# Anode.net
KiCad netlist of a schematic drawn in Altium Designer
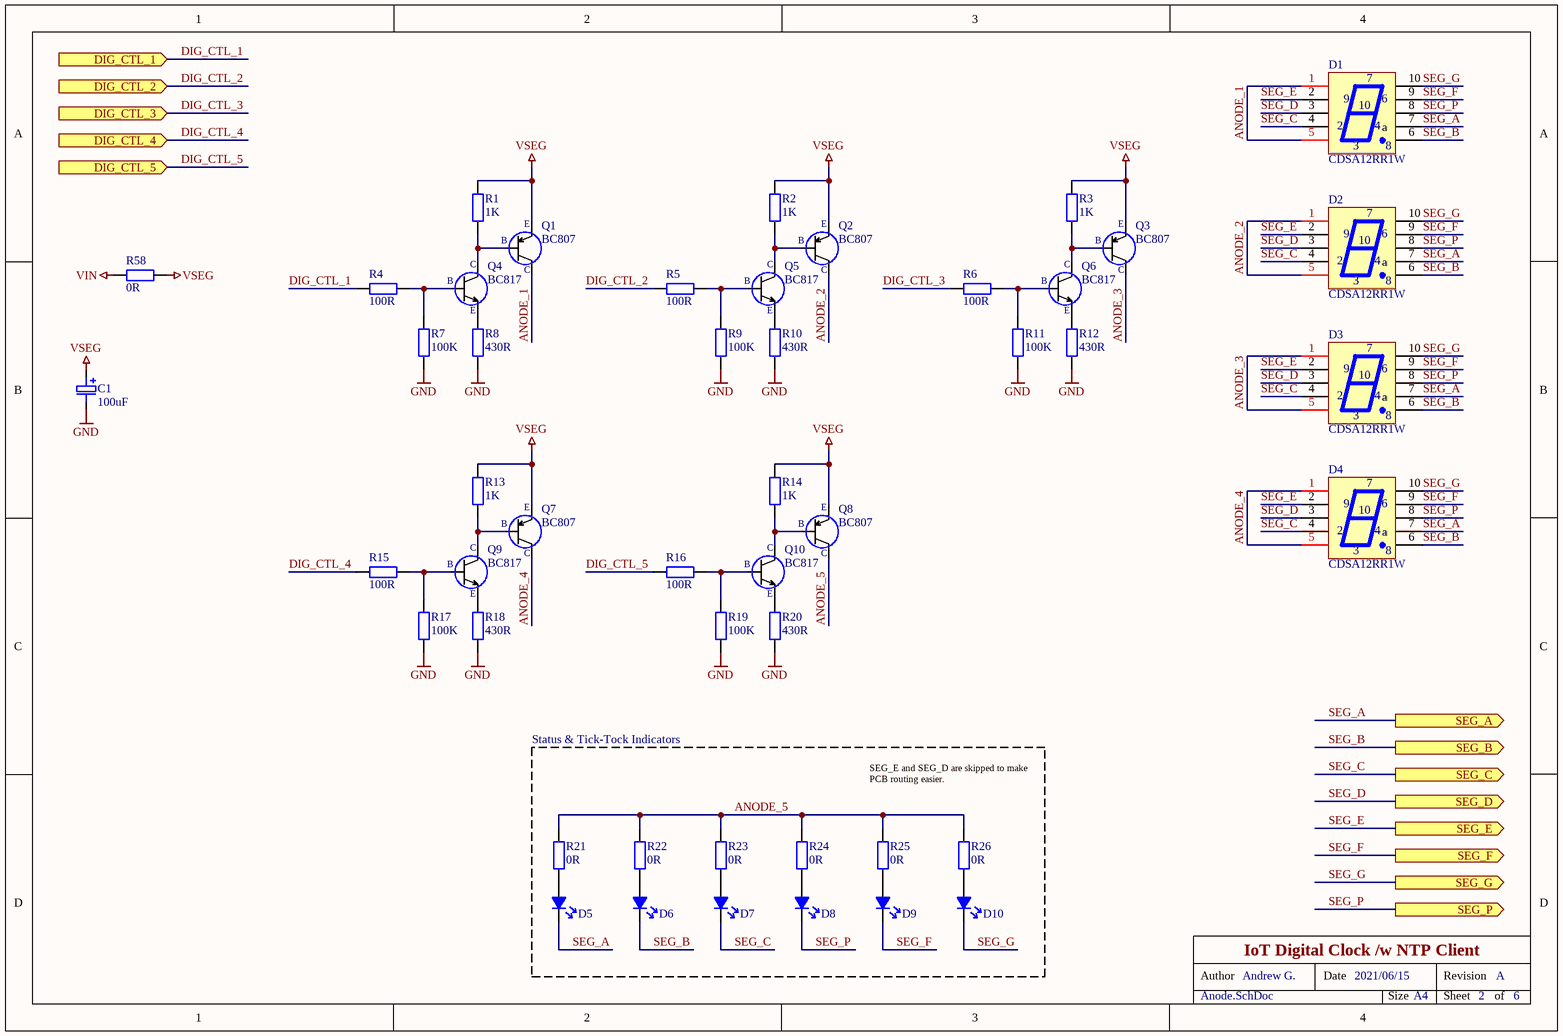
[diagram p0: Anode.SchDoc]

(export (version "E")
  (design (tool "Eeschema 10.0.6"))
  (components
    (comp (ref "C1")
      (value "100uF")
      (footprint "C_EL_B_4MM_RF_M")
      (description "Polarized Capacitor")
      (fields (field (name "TOLERANCE") "?") (field (name "MANUFACTURER") "Generic Brand"))
      (libsource (lib "AG.Generic") (part "C-P"))
    )
    (comp (ref "D1")
      (value "CDSA12RR1W")
      (footprint "CDSX12")
      (description "DISPLAY 7SEG 1.20\" SGL RED 10DIP")
      (libsource (lib "AG.Passive") (part "CDSA12RR1W"))
    )
    (comp (ref "D2")
      (value "CDSA12RR1W")
      (footprint "CDSX12")
      (description "DISPLAY 7SEG 1.20\" SGL RED 10DIP")
      (libsource (lib "AG.Passive") (part "CDSA12RR1W"))
    )
    (comp (ref "D3")
      (value "CDSA12RR1W")
      (footprint "CDSX12")
      (description "DISPLAY 7SEG 1.20\" SGL RED 10DIP")
      (libsource (lib "AG.Passive") (part "CDSA12RR1W"))
    )
    (comp (ref "D4")
      (value "CDSA12RR1W")
      (footprint "CDSX12")
      (description "DISPLAY 7SEG 1.20\" SGL RED 10DIP")
      (libsource (lib "AG.Passive") (part "CDSA12RR1W"))
    )
    (comp (ref "D5")
      (value "Unspecified")
      (footprint "1206LED_RF_M")
      (description "LED")
      (fields (field (name "MANUFACTURER") "Generic Brand"))
      (libsource (lib "AG.Generic") (part "LED"))
    )
    (comp (ref "D6")
      (value "Unspecified")
      (footprint "1206LED_RF_M")
      (description "LED")
      (fields (field (name "MANUFACTURER") "Generic Brand"))
      (libsource (lib "AG.Generic") (part "LED"))
    )
    (comp (ref "D7")
      (value "Unspecified")
      (footprint "1206LED_RF_M")
      (description "LED")
      (fields (field (name "MANUFACTURER") "Generic Brand"))
      (libsource (lib "AG.Generic") (part "LED"))
    )
    (comp (ref "D8")
      (value "Unspecified")
      (footprint "1206LED_RF_M")
      (description "LED")
      (fields (field (name "MANUFACTURER") "Generic Brand"))
      (libsource (lib "AG.Generic") (part "LED"))
    )
    (comp (ref "D9")
      (value "Unspecified")
      (footprint "1206LED_RF_M")
      (description "LED")
      (fields (field (name "MANUFACTURER") "Generic Brand"))
      (libsource (lib "AG.Generic") (part "LED"))
    )
    (comp (ref "D10")
      (value "Unspecified")
      (footprint "1206LED_RF_M")
      (description "LED")
      (fields (field (name "MANUFACTURER") "Generic Brand"))
      (libsource (lib "AG.Generic") (part "LED"))
    )
    (comp (ref "Q1")
      (value "BC807")
      (footprint "IRLML_SOT-23")
      (description "TRANS PNP 45V 500MA TO236AB")
      (fields (field (name "ALTERNATIVE SUPPLIER PART NO") "9000113306"))
      (libsource (lib "AG.Discrete") (part "BC807-215"))
    )
    (comp (ref "Q2")
      (value "BC807")
      (footprint "IRLML_SOT-23")
      (description "TRANS PNP 45V 500MA TO236AB")
      (fields (field (name "ALTERNATIVE SUPPLIER PART NO") "9000113306"))
      (libsource (lib "AG.Discrete") (part "BC807-215"))
    )
    (comp (ref "Q3")
      (value "BC807")
      (footprint "IRLML_SOT-23")
      (description "TRANS PNP 45V 500MA TO236AB")
      (fields (field (name "ALTERNATIVE SUPPLIER PART NO") "9000113306"))
      (libsource (lib "AG.Discrete") (part "BC807-215"))
    )
    (comp (ref "Q4")
      (value "BC817")
      (footprint "IRLML_SOT-23")
      (description "TRANS NPN 45V 0.5A SOT23")
      (fields
        (field (name "MANUFACTURER") "Nexperia USA Inc.")
        (field (name "MANUFACTURER PART NO") "BC817-40,215")
      )
      (libsource (lib "AG.Discrete") (part "BC817-40-215"))
    )
    (comp (ref "Q5")
      (value "BC817")
      (footprint "IRLML_SOT-23")
      (description "TRANS NPN 45V 0.5A SOT23")
      (fields
        (field (name "MANUFACTURER") "Nexperia USA Inc.")
        (field (name "MANUFACTURER PART NO") "BC817-40,215")
      )
      (libsource (lib "AG.Discrete") (part "BC817-40-215"))
    )
    (comp (ref "Q6")
      (value "BC817")
      (footprint "IRLML_SOT-23")
      (description "TRANS NPN 45V 0.5A SOT23")
      (fields
        (field (name "MANUFACTURER") "Nexperia USA Inc.")
        (field (name "MANUFACTURER PART NO") "BC817-40,215")
      )
      (libsource (lib "AG.Discrete") (part "BC817-40-215"))
    )
    (comp (ref "Q7")
      (value "BC807")
      (footprint "IRLML_SOT-23")
      (description "TRANS PNP 45V 500MA TO236AB")
      (fields (field (name "ALTERNATIVE SUPPLIER PART NO") "9000113306"))
      (libsource (lib "AG.Discrete") (part "BC807-215"))
    )
    (comp (ref "Q8")
      (value "BC807")
      (footprint "IRLML_SOT-23")
      (description "TRANS PNP 45V 500MA TO236AB")
      (fields (field (name "ALTERNATIVE SUPPLIER PART NO") "9000113306"))
      (libsource (lib "AG.Discrete") (part "BC807-215"))
    )
    (comp (ref "Q9")
      (value "BC817")
      (footprint "IRLML_SOT-23")
      (description "TRANS NPN 45V 0.5A SOT23")
      (fields
        (field (name "MANUFACTURER") "Nexperia USA Inc.")
        (field (name "MANUFACTURER PART NO") "BC817-40,215")
      )
      (libsource (lib "AG.Discrete") (part "BC817-40-215"))
    )
    (comp (ref "Q10")
      (value "BC817")
      (footprint "IRLML_SOT-23")
      (description "TRANS NPN 45V 0.5A SOT23")
      (fields
        (field (name "MANUFACTURER") "Nexperia USA Inc.")
        (field (name "MANUFACTURER PART NO") "BC817-40,215")
      )
      (libsource (lib "AG.Discrete") (part "BC817-40-215"))
    )
    (comp (ref "R1")
      (value "1K")
      (footprint "0805R_RF_M")
      (description "Resistor")
      (fields (field (name "TOLERANCE") "?") (field (name "MANUFACTURER") "Generic Brand"))
      (libsource (lib "AG.Generic") (part "R"))
    )
    (comp (ref "R2")
      (value "1K")
      (footprint "0805R_RF_M")
      (description "Resistor")
      (fields (field (name "TOLERANCE") "?") (field (name "MANUFACTURER") "Generic Brand"))
      (libsource (lib "AG.Generic") (part "R"))
    )
    (comp (ref "R3")
      (value "1K")
      (footprint "0805R_RF_M")
      (description "Resistor")
      (fields (field (name "TOLERANCE") "?") (field (name "MANUFACTURER") "Generic Brand"))
      (libsource (lib "AG.Generic") (part "R"))
    )
    (comp (ref "R4")
      (value "100R")
      (footprint "0805R_RF_M")
      (description "Resistor")
      (fields (field (name "TOLERANCE") "?") (field (name "MANUFACTURER") "Generic Brand"))
      (libsource (lib "AG.Generic") (part "R"))
    )
    (comp (ref "R5")
      (value "100R")
      (footprint "0805R_RF_M")
      (description "Resistor")
      (fields (field (name "TOLERANCE") "?") (field (name "MANUFACTURER") "Generic Brand"))
      (libsource (lib "AG.Generic") (part "R"))
    )
    (comp (ref "R6")
      (value "100R")
      (footprint "0805R_RF_M")
      (description "Resistor")
      (fields (field (name "TOLERANCE") "?") (field (name "MANUFACTURER") "Generic Brand"))
      (libsource (lib "AG.Generic") (part "R"))
    )
    (comp (ref "R7")
      (value "100K")
      (footprint "0805R_RF_M")
      (description "Resistor")
      (fields (field (name "TOLERANCE") "?") (field (name "MANUFACTURER") "Generic Brand"))
      (libsource (lib "AG.Generic") (part "R"))
    )
    (comp (ref "R8")
      (value "430R")
      (footprint "0805R_RF_M")
      (description "Resistor")
      (fields (field (name "TOLERANCE") "?") (field (name "MANUFACTURER") "Generic Brand"))
      (libsource (lib "AG.Generic") (part "R"))
    )
    (comp (ref "R9")
      (value "100K")
      (footprint "0805R_RF_M")
      (description "Resistor")
      (fields (field (name "TOLERANCE") "?") (field (name "MANUFACTURER") "Generic Brand"))
      (libsource (lib "AG.Generic") (part "R"))
    )
    (comp (ref "R10")
      (value "430R")
      (footprint "0805R_RF_M")
      (description "Resistor")
      (fields (field (name "TOLERANCE") "?") (field (name "MANUFACTURER") "Generic Brand"))
      (libsource (lib "AG.Generic") (part "R"))
    )
    (comp (ref "R11")
      (value "100K")
      (footprint "0805R_RF_M")
      (description "Resistor")
      (fields (field (name "TOLERANCE") "?") (field (name "MANUFACTURER") "Generic Brand"))
      (libsource (lib "AG.Generic") (part "R"))
    )
    (comp (ref "R12")
      (value "430R")
      (footprint "0805R_RF_M")
      (description "Resistor")
      (fields (field (name "TOLERANCE") "?") (field (name "MANUFACTURER") "Generic Brand"))
      (libsource (lib "AG.Generic") (part "R"))
    )
    (comp (ref "R13")
      (value "1K")
      (footprint "0805R_RF_M")
      (description "Resistor")
      (fields (field (name "TOLERANCE") "?") (field (name "MANUFACTURER") "Generic Brand"))
      (libsource (lib "AG.Generic") (part "R"))
    )
    (comp (ref "R14")
      (value "1K")
      (footprint "0805R_RF_M")
      (description "Resistor")
      (fields (field (name "TOLERANCE") "?") (field (name "MANUFACTURER") "Generic Brand"))
      (libsource (lib "AG.Generic") (part "R"))
    )
    (comp (ref "R15")
      (value "100R")
      (footprint "0805R_RF_M")
      (description "Resistor")
      (fields (field (name "TOLERANCE") "?") (field (name "MANUFACTURER") "Generic Brand"))
      (libsource (lib "AG.Generic") (part "R"))
    )
    (comp (ref "R16")
      (value "100R")
      (footprint "0805R_RF_M")
      (description "Resistor")
      (fields (field (name "TOLERANCE") "?") (field (name "MANUFACTURER") "Generic Brand"))
      (libsource (lib "AG.Generic") (part "R"))
    )
    (comp (ref "R17")
      (value "100K")
      (footprint "0805R_RF_M")
      (description "Resistor")
      (fields (field (name "TOLERANCE") "?") (field (name "MANUFACTURER") "Generic Brand"))
      (libsource (lib "AG.Generic") (part "R"))
    )
    (comp (ref "R18")
      (value "430R")
      (footprint "0805R_RF_M")
      (description "Resistor")
      (fields (field (name "TOLERANCE") "?") (field (name "MANUFACTURER") "Generic Brand"))
      (libsource (lib "AG.Generic") (part "R"))
    )
    (comp (ref "R19")
      (value "100K")
      (footprint "0805R_RF_M")
      (description "Resistor")
      (fields (field (name "TOLERANCE") "?") (field (name "MANUFACTURER") "Generic Brand"))
      (libsource (lib "AG.Generic") (part "R"))
    )
    (comp (ref "R20")
      (value "430R")
      (footprint "0805R_RF_M")
      (description "Resistor")
      (fields (field (name "TOLERANCE") "?") (field (name "MANUFACTURER") "Generic Brand"))
      (libsource (lib "AG.Generic") (part "R"))
    )
    (comp (ref "R21")
      (value "0R")
      (footprint "0805R_RF_M")
      (description "Resistor")
      (fields (field (name "TOLERANCE") "?") (field (name "MANUFACTURER") "Generic Brand"))
      (libsource (lib "AG.Generic") (part "R"))
    )
    (comp (ref "R22")
      (value "0R")
      (footprint "0805R_RF_M")
      (description "Resistor")
      (fields (field (name "TOLERANCE") "?") (field (name "MANUFACTURER") "Generic Brand"))
      (libsource (lib "AG.Generic") (part "R"))
    )
    (comp (ref "R23")
      (value "0R")
      (footprint "0805R_RF_M")
      (description "Resistor")
      (fields (field (name "TOLERANCE") "?") (field (name "MANUFACTURER") "Generic Brand"))
      (libsource (lib "AG.Generic") (part "R"))
    )
    (comp (ref "R24")
      (value "0R")
      (footprint "0805R_RF_M")
      (description "Resistor")
      (fields (field (name "TOLERANCE") "?") (field (name "MANUFACTURER") "Generic Brand"))
      (libsource (lib "AG.Generic") (part "R"))
    )
    (comp (ref "R25")
      (value "0R")
      (footprint "0805R_RF_M")
      (description "Resistor")
      (fields (field (name "TOLERANCE") "?") (field (name "MANUFACTURER") "Generic Brand"))
      (libsource (lib "AG.Generic") (part "R"))
    )
    (comp (ref "R26")
      (value "0R")
      (footprint "0805R_RF_M")
      (description "Resistor")
      (fields (field (name "TOLERANCE") "?") (field (name "MANUFACTURER") "Generic Brand"))
      (libsource (lib "AG.Generic") (part "R"))
    )
    (comp (ref "R58")
      (value "0R")
      (footprint "1206R_RF_M")
      (description "Resistor")
      (fields (field (name "TOLERANCE") "?") (field (name "MANUFACTURER") "Generic Brand"))
      (libsource (lib "AG.Generic") (part "R"))
    )
  )
  (nets
    (net (code "1") (name "/ANODE_1") (class "Default")
      (node (ref "D1") (pin "1") (pinfunction "A_1") (pintype "passive"))
      (node (ref "D1") (pin "5") (pinfunction "A_5") (pintype "passive"))
      (node (ref "Q1") (pin "3") (pinfunction "Collector_3") (pintype "passive"))
    )
    (net (code "2") (name "/ANODE_2") (class "Default")
      (node (ref "D2") (pin "1") (pinfunction "A_1") (pintype "passive"))
      (node (ref "D2") (pin "5") (pinfunction "A_5") (pintype "passive"))
      (node (ref "Q2") (pin "3") (pinfunction "Collector_3") (pintype "passive"))
    )
    (net (code "3") (name "/ANODE_3") (class "Default")
      (node (ref "D3") (pin "1") (pinfunction "A_1") (pintype "passive"))
      (node (ref "D3") (pin "5") (pinfunction "A_5") (pintype "passive"))
      (node (ref "Q3") (pin "3") (pinfunction "Collector_3") (pintype "passive"))
    )
    (net (code "4") (name "/ANODE_4") (class "Default")
      (node (ref "D4") (pin "1") (pinfunction "A_1") (pintype "passive"))
      (node (ref "D4") (pin "5") (pinfunction "A_5") (pintype "passive"))
      (node (ref "Q7") (pin "3") (pinfunction "Collector_3") (pintype "passive"))
    )
    (net (code "5") (name "/ANODE_5") (class "Default")
      (node (ref "Q8") (pin "3") (pinfunction "Collector_3") (pintype "passive"))
      (node (ref "R21") (pin "2") (pintype "passive"))
      (node (ref "R22") (pin "2") (pintype "passive"))
      (node (ref "R23") (pin "2") (pintype "passive"))
      (node (ref "R24") (pin "2") (pintype "passive"))
      (node (ref "R25") (pin "2") (pintype "passive"))
      (node (ref "R26") (pin "2") (pintype "passive"))
    )
    (net (code "6") (name "/DIG_CTL_1") (class "Default") (node (ref "R4") (pin "1") (pintype "passive")))
    (net (code "7") (name "/DIG_CTL_2") (class "Default") (node (ref "R5") (pin "1") (pintype "passive")))
    (net (code "8") (name "/DIG_CTL_3") (class "Default") (node (ref "R6") (pin "1") (pintype "passive")))
    (net (code "9") (name "/DIG_CTL_4") (class "Default") (node (ref "R15") (pin "1") (pintype "passive")))
    (net (code "10") (name "/DIG_CTL_5") (class "Default") (node (ref "R16") (pin "1") (pintype "passive")))
    (net (code "11") (name "/SEG_A") (class "Default")
      (node (ref "D1") (pin "7") (pinfunction "a_7") (pintype "passive"))
      (node (ref "D2") (pin "7") (pinfunction "a_7") (pintype "passive"))
      (node (ref "D3") (pin "7") (pinfunction "a_7") (pintype "passive"))
      (node (ref "D4") (pin "7") (pinfunction "a_7") (pintype "passive"))
      (node (ref "D5") (pin "C") (pinfunction "C_C") (pintype "passive"))
    )
    (net (code "12") (name "/SEG_B") (class "Default")
      (node (ref "D1") (pin "6") (pinfunction "b_6") (pintype "passive"))
      (node (ref "D2") (pin "6") (pinfunction "b_6") (pintype "passive"))
      (node (ref "D3") (pin "6") (pinfunction "b_6") (pintype "passive"))
      (node (ref "D4") (pin "6") (pinfunction "b_6") (pintype "passive"))
      (node (ref "D6") (pin "C") (pinfunction "C_C") (pintype "passive"))
    )
    (net (code "13") (name "/SEG_C") (class "Default")
      (node (ref "D1") (pin "4") (pinfunction "c_4") (pintype "passive"))
      (node (ref "D2") (pin "4") (pinfunction "c_4") (pintype "passive"))
      (node (ref "D3") (pin "4") (pinfunction "c_4") (pintype "passive"))
      (node (ref "D4") (pin "4") (pinfunction "c_4") (pintype "passive"))
      (node (ref "D7") (pin "C") (pinfunction "C_C") (pintype "passive"))
    )
    (net (code "14") (name "/SEG_D") (class "Default")
      (node (ref "D1") (pin "3") (pinfunction "d_3") (pintype "passive"))
      (node (ref "D2") (pin "3") (pinfunction "d_3") (pintype "passive"))
      (node (ref "D3") (pin "3") (pinfunction "d_3") (pintype "passive"))
      (node (ref "D4") (pin "3") (pinfunction "d_3") (pintype "passive"))
    )
    (net (code "15") (name "/SEG_E") (class "Default")
      (node (ref "D1") (pin "2") (pinfunction "e_2") (pintype "passive"))
      (node (ref "D2") (pin "2") (pinfunction "e_2") (pintype "passive"))
      (node (ref "D3") (pin "2") (pinfunction "e_2") (pintype "passive"))
      (node (ref "D4") (pin "2") (pinfunction "e_2") (pintype "passive"))
    )
    (net (code "16") (name "/SEG_F") (class "Default")
      (node (ref "D1") (pin "9") (pinfunction "f_9") (pintype "passive"))
      (node (ref "D2") (pin "9") (pinfunction "f_9") (pintype "passive"))
      (node (ref "D3") (pin "9") (pinfunction "f_9") (pintype "passive"))
      (node (ref "D4") (pin "9") (pinfunction "f_9") (pintype "passive"))
      (node (ref "D9") (pin "C") (pinfunction "C_C") (pintype "passive"))
    )
    (net (code "17") (name "/SEG_G") (class "Default")
      (node (ref "D1") (pin "10") (pinfunction "g_10") (pintype "passive"))
      (node (ref "D10") (pin "C") (pinfunction "C_C") (pintype "passive"))
      (node (ref "D2") (pin "10") (pinfunction "g_10") (pintype "passive"))
      (node (ref "D3") (pin "10") (pinfunction "g_10") (pintype "passive"))
      (node (ref "D4") (pin "10") (pinfunction "g_10") (pintype "passive"))
    )
    (net (code "18") (name "/SEG_P") (class "Default")
      (node (ref "D1") (pin "8") (pinfunction "dp_8") (pintype "passive"))
      (node (ref "D2") (pin "8") (pinfunction "dp_8") (pintype "passive"))
      (node (ref "D3") (pin "8") (pinfunction "dp_8") (pintype "passive"))
      (node (ref "D4") (pin "8") (pinfunction "dp_8") (pintype "passive"))
      (node (ref "D8") (pin "C") (pinfunction "C_C") (pintype "passive"))
    )
    (net (code "19") (name "GND") (class "Default")
      (node (ref "C1") (pin "N") (pinfunction "N_N") (pintype "power_in"))
      (node (ref "R10") (pin "1") (pintype "passive"))
      (node (ref "R11") (pin "1") (pintype "passive"))
      (node (ref "R12") (pin "1") (pintype "passive"))
      (node (ref "R17") (pin "1") (pintype "passive"))
      (node (ref "R18") (pin "1") (pintype "passive"))
      (node (ref "R19") (pin "1") (pintype "passive"))
      (node (ref "R20") (pin "1") (pintype "passive"))
      (node (ref "R7") (pin "1") (pintype "passive"))
      (node (ref "R8") (pin "1") (pintype "passive"))
      (node (ref "R9") (pin "1") (pintype "passive"))
    )
    (net (code "20") (name "Net-(D5-PadA)") (class "Default")
      (node (ref "D5") (pin "A") (pinfunction "A_A") (pintype "passive"))
      (node (ref "R21") (pin "1") (pintype "passive"))
    )
    (net (code "21") (name "Net-(D6-PadA)") (class "Default")
      (node (ref "D6") (pin "A") (pinfunction "A_A") (pintype "passive"))
      (node (ref "R22") (pin "1") (pintype "passive"))
    )
    (net (code "22") (name "Net-(D7-PadA)") (class "Default")
      (node (ref "D7") (pin "A") (pinfunction "A_A") (pintype "passive"))
      (node (ref "R23") (pin "1") (pintype "passive"))
    )
    (net (code "23") (name "Net-(D8-PadA)") (class "Default")
      (node (ref "D8") (pin "A") (pinfunction "A_A") (pintype "passive"))
      (node (ref "R24") (pin "1") (pintype "passive"))
    )
    (net (code "24") (name "Net-(D9-PadA)") (class "Default")
      (node (ref "D9") (pin "A") (pinfunction "A_A") (pintype "passive"))
      (node (ref "R25") (pin "1") (pintype "passive"))
    )
    (net (code "25") (name "Net-(D10-PadA)") (class "Default")
      (node (ref "D10") (pin "A") (pinfunction "A_A") (pintype "passive"))
      (node (ref "R26") (pin "1") (pintype "passive"))
    )
    (net (code "26") (name "Net-(Q1-Base)") (class "Default")
      (node (ref "Q1") (pin "1") (pinfunction "Base_1") (pintype "passive"))
      (node (ref "Q4") (pin "3") (pinfunction "Collector_3") (pintype "passive"))
      (node (ref "R1") (pin "1") (pintype "passive"))
    )
    (net (code "27") (name "Net-(Q2-Base)") (class "Default")
      (node (ref "Q2") (pin "1") (pinfunction "Base_1") (pintype "passive"))
      (node (ref "Q5") (pin "3") (pinfunction "Collector_3") (pintype "passive"))
      (node (ref "R2") (pin "1") (pintype "passive"))
    )
    (net (code "28") (name "Net-(Q3-Base)") (class "Default")
      (node (ref "Q3") (pin "1") (pinfunction "Base_1") (pintype "passive"))
      (node (ref "Q6") (pin "3") (pinfunction "Collector_3") (pintype "passive"))
      (node (ref "R3") (pin "1") (pintype "passive"))
    )
    (net (code "29") (name "Net-(Q4-Base)") (class "Default")
      (node (ref "Q4") (pin "1") (pinfunction "Base_1") (pintype "passive"))
      (node (ref "R4") (pin "2") (pintype "passive"))
      (node (ref "R7") (pin "2") (pintype "passive"))
    )
    (net (code "30") (name "Net-(Q4-Emmiter)") (class "Default")
      (node (ref "Q4") (pin "2") (pinfunction "Emmiter_2") (pintype "passive"))
      (node (ref "R8") (pin "2") (pintype "passive"))
    )
    (net (code "31") (name "Net-(Q5-Base)") (class "Default")
      (node (ref "Q5") (pin "1") (pinfunction "Base_1") (pintype "passive"))
      (node (ref "R5") (pin "2") (pintype "passive"))
      (node (ref "R9") (pin "2") (pintype "passive"))
    )
    (net (code "32") (name "Net-(Q5-Emmiter)") (class "Default")
      (node (ref "Q5") (pin "2") (pinfunction "Emmiter_2") (pintype "passive"))
      (node (ref "R10") (pin "2") (pintype "passive"))
    )
    (net (code "33") (name "Net-(Q6-Base)") (class "Default")
      (node (ref "Q6") (pin "1") (pinfunction "Base_1") (pintype "passive"))
      (node (ref "R11") (pin "2") (pintype "passive"))
      (node (ref "R6") (pin "2") (pintype "passive"))
    )
    (net (code "34") (name "Net-(Q6-Emmiter)") (class "Default")
      (node (ref "Q6") (pin "2") (pinfunction "Emmiter_2") (pintype "passive"))
      (node (ref "R12") (pin "2") (pintype "passive"))
    )
    (net (code "35") (name "Net-(Q7-Base)") (class "Default")
      (node (ref "Q7") (pin "1") (pinfunction "Base_1") (pintype "passive"))
      (node (ref "Q9") (pin "3") (pinfunction "Collector_3") (pintype "passive"))
      (node (ref "R13") (pin "1") (pintype "passive"))
    )
    (net (code "36") (name "Net-(Q9-Base)") (class "Default")
      (node (ref "Q9") (pin "1") (pinfunction "Base_1") (pintype "passive"))
      (node (ref "R15") (pin "2") (pintype "passive"))
      (node (ref "R17") (pin "2") (pintype "passive"))
    )
    (net (code "37") (name "Net-(Q9-Emmiter)") (class "Default")
      (node (ref "Q9") (pin "2") (pinfunction "Emmiter_2") (pintype "passive"))
      (node (ref "R18") (pin "2") (pintype "passive"))
    )
    (net (code "38") (name "Net-(Q10-Base)") (class "Default")
      (node (ref "Q10") (pin "1") (pinfunction "Base_1") (pintype "passive"))
      (node (ref "R16") (pin "2") (pintype "passive"))
      (node (ref "R19") (pin "2") (pintype "passive"))
    )
    (net (code "39") (name "Net-(Q10-Collector)") (class "Default")
      (node (ref "Q10") (pin "3") (pinfunction "Collector_3") (pintype "passive"))
      (node (ref "Q8") (pin "1") (pinfunction "Base_1") (pintype "passive"))
      (node (ref "R14") (pin "1") (pintype "passive"))
    )
    (net (code "40") (name "Net-(Q10-Emmiter)") (class "Default")
      (node (ref "Q10") (pin "2") (pinfunction "Emmiter_2") (pintype "passive"))
      (node (ref "R20") (pin "2") (pintype "passive"))
    )
    (net (code "41") (name "VIN") (class "Default") (node (ref "R58") (pin "1") (pintype "passive")))
    (net (code "42") (name "VSEG") (class "Default")
      (node (ref "C1") (pin "P") (pinfunction "P_P") (pintype "power_in"))
      (node (ref "Q1") (pin "2") (pinfunction "Emmiter_2") (pintype "passive"))
      (node (ref "Q2") (pin "2") (pinfunction "Emmiter_2") (pintype "passive"))
      (node (ref "Q3") (pin "2") (pinfunction "Emmiter_2") (pintype "passive"))
      (node (ref "Q7") (pin "2") (pinfunction "Emmiter_2") (pintype "passive"))
      (node (ref "Q8") (pin "2") (pinfunction "Emmiter_2") (pintype "passive"))
      (node (ref "R1") (pin "2") (pintype "passive"))
      (node (ref "R13") (pin "2") (pintype "passive"))
      (node (ref "R14") (pin "2") (pintype "passive"))
      (node (ref "R2") (pin "2") (pintype "passive"))
      (node (ref "R3") (pin "2") (pintype "passive"))
      (node (ref "R58") (pin "2") (pintype "passive"))
    )
  )
)
